# licznik.net
KiCad netlist of a schematic drawn in EAGLE
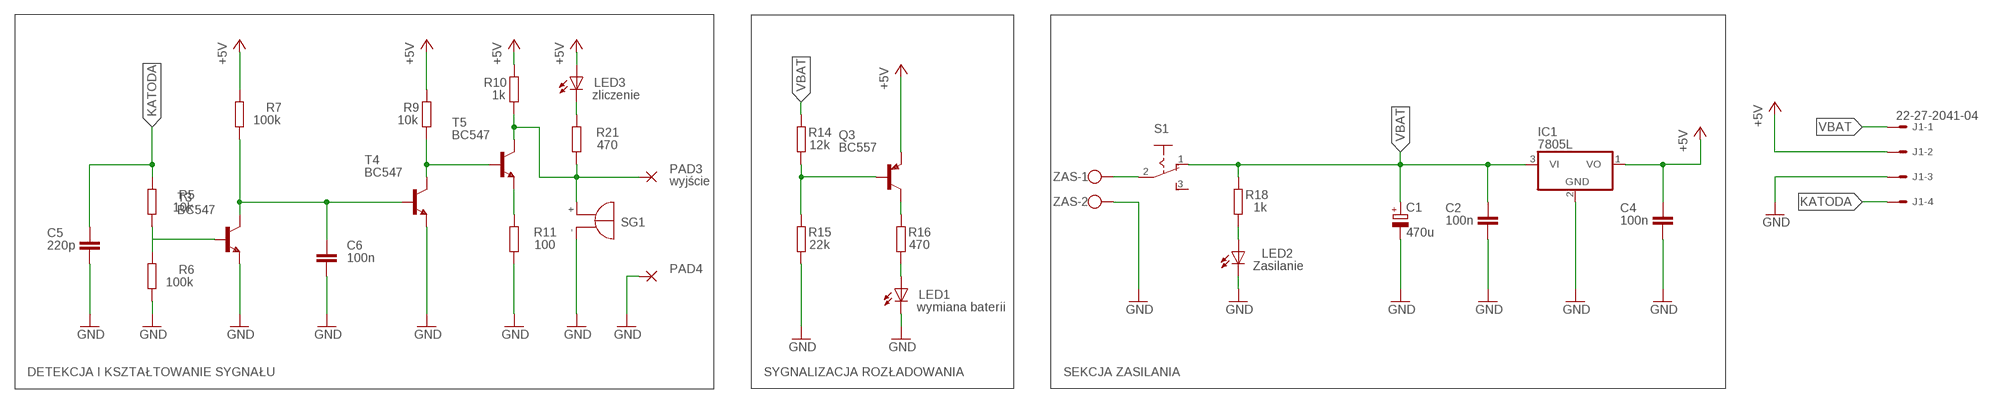
[diagram p0: schematic, sheet 1]

(export (version "E")
  (design (tool "Eeschema 10.0.6"))
  (components
    (comp (ref "C1")
      (value "470u")
      (footprint "eagle-import:E3,5-8")
      (libsource (lib "eagle-import") (part "CPOL-EUE3.5-8"))
    )
    (comp (ref "C2")
      (value "100n")
      (footprint "eagle-import:C5B3")
      (libsource (lib "eagle-import") (part "C5/3"))
    )
    (comp (ref "C4")
      (value "100n")
      (footprint "eagle-import:C5B3")
      (libsource (lib "eagle-import") (part "C5/3"))
    )
    (comp (ref "C5")
      (value "220p")
      (footprint "eagle-import:C5B3")
      (libsource (lib "eagle-import") (part "C5/3"))
    )
    (comp (ref "C6")
      (value "100n")
      (footprint "eagle-import:C5B3")
      (libsource (lib "eagle-import") (part "C5/3"))
    )
    (comp (ref "IC1")
      (value "7805L")
      (footprint "eagle-import:TO92")
      (libsource (lib "eagle-import") (part "78L05"))
    )
    (comp (ref "J1")
      (value "22-27-2041-04")
      (footprint "eagle-import:6410-04")
      (libsource (lib "eagle-import") (part "22-?-0427-2041"))
    )
    (comp (ref "LED1")
      (value "wymiana baterii")
      (footprint "eagle-import:LED3MM")
      (libsource (lib "eagle-import") (part "LED3MM"))
    )
    (comp (ref "LED2")
      (value "Zasilanie")
      (footprint "eagle-import:LED3MM")
      (libsource (lib "eagle-import") (part "LED3MM"))
    )
    (comp (ref "LED3")
      (value "zliczenie")
      (footprint "eagle-import:LED3MM")
      (libsource (lib "eagle-import") (part "LED3MM"))
    )
    (comp (ref "PAD3")
      (value "wyjście")
      (footprint "eagle-import:2,15_1,0")
      (libsource (lib "eagle-import") (part "WIREPAD2,15/1,0"))
    )
    (comp (ref "PAD4")
      (value "WIREPAD2,15/1,0")
      (footprint "eagle-import:2,15_1,0")
      (libsource (lib "eagle-import") (part "WIREPAD2,15/1,0"))
    )
    (comp (ref "Q3")
      (value "BC557")
      (footprint "eagle-import:TO92")
      (libsource (lib "eagle-import") (part "BC557"))
    )
    (comp (ref "R5")
      (value "10k")
      (footprint "eagle-import:0207_10")
      (libsource (lib "eagle-import") (part "R-EU_0207/10"))
    )
    (comp (ref "R6")
      (value "100k")
      (footprint "eagle-import:0207_10")
      (libsource (lib "eagle-import") (part "R-EU_0207/10"))
    )
    (comp (ref "R7")
      (value "100k")
      (footprint "eagle-import:0207_10")
      (libsource (lib "eagle-import") (part "R-EU_0207/10"))
    )
    (comp (ref "R9")
      (value "10k")
      (footprint "eagle-import:0207_10")
      (libsource (lib "eagle-import") (part "R-EU_0207/10"))
    )
    (comp (ref "R10")
      (value "1k")
      (footprint "eagle-import:0207_10")
      (libsource (lib "eagle-import") (part "R-EU_0207/10"))
    )
    (comp (ref "R11")
      (value "100")
      (footprint "eagle-import:0207_10")
      (libsource (lib "eagle-import") (part "R-EU_0207/10"))
    )
    (comp (ref "R14")
      (value "12k")
      (footprint "eagle-import:0207_10")
      (libsource (lib "eagle-import") (part "R-EU_0207/10"))
    )
    (comp (ref "R15")
      (value "22k")
      (footprint "eagle-import:0207_10")
      (libsource (lib "eagle-import") (part "R-EU_0207/10"))
    )
    (comp (ref "R16")
      (value "470")
      (footprint "eagle-import:0207_10")
      (libsource (lib "eagle-import") (part "R-EU_0207/10"))
    )
    (comp (ref "R18")
      (value "1k")
      (footprint "eagle-import:0207_10")
      (libsource (lib "eagle-import") (part "R-EU_0207/10"))
    )
    (comp (ref "R21")
      (value "470")
      (footprint "eagle-import:0207_10")
      (libsource (lib "eagle-import") (part "R-EU_0207/10"))
    )
    (comp (ref "S1")
      (value "255SB")
      (footprint "eagle-import:255SB")
      (libsource (lib "eagle-import") (part "255SB"))
    )
    (comp (ref "SG1")
      (value "F/QMBIII")
      (footprint "eagle-import:F_QMBIII")
      (libsource (lib "eagle-import") (part "F/QMBIII"))
    )
    (comp (ref "T3")
      (value "BC547")
      (footprint "eagle-import:TO92")
      (libsource (lib "eagle-import") (part "BC547"))
    )
    (comp (ref "T4")
      (value "BC547")
      (footprint "eagle-import:TO92")
      (libsource (lib "eagle-import") (part "BC547"))
    )
    (comp (ref "T5")
      (value "BC547")
      (footprint "eagle-import:TO92")
      (libsource (lib "eagle-import") (part "BC547"))
    )
    (comp (ref "ZAS")
      (value "W237-102")
      (footprint "eagle-import:W237-102")
      (fields (field (name "MPN") "237-102"))
      (libsource (lib "eagle-import") (part "W237-102"))
    )
  )
  (nets
    (net (code "1") (name "+5V") (class "Default")
      (node (ref "C4") (pin "1") (pinfunction "1_1") (pintype "passive"))
      (node (ref "IC1") (pin "1") (pinfunction "VO_1") (pintype "passive"))
      (node (ref "J1") (pin "2") (pinfunction "S_2") (pintype "passive"))
      (node (ref "LED3") (pin "A") (pinfunction "A_A") (pintype "passive"))
      (node (ref "Q3") (pin "1") (pinfunction "E_1") (pintype "passive"))
      (node (ref "R10") (pin "2") (pinfunction "2_2") (pintype "passive"))
      (node (ref "R7") (pin "2") (pinfunction "2_2") (pintype "passive"))
      (node (ref "R9") (pin "2") (pinfunction "2_2") (pintype "passive"))
    )
    (net (code "2") (name "GND") (class "Default")
      (node (ref "C1") (pin "-") (pinfunction "-_-") (pintype "passive"))
      (node (ref "C2") (pin "2") (pinfunction "2_2") (pintype "passive"))
      (node (ref "C4") (pin "2") (pinfunction "2_2") (pintype "passive"))
      (node (ref "C5") (pin "2") (pinfunction "2_2") (pintype "passive"))
      (node (ref "C6") (pin "2") (pinfunction "2_2") (pintype "passive"))
      (node (ref "IC1") (pin "2") (pinfunction "GND_2") (pintype "passive"))
      (node (ref "J1") (pin "3") (pinfunction "S_3") (pintype "passive"))
      (node (ref "LED1") (pin "K") (pinfunction "C_K") (pintype "passive"))
      (node (ref "LED2") (pin "K") (pinfunction "C_K") (pintype "passive"))
      (node (ref "PAD4") (pin "1") (pinfunction "P_1") (pintype "passive"))
      (node (ref "R11") (pin "1") (pinfunction "1_1") (pintype "passive"))
      (node (ref "R15") (pin "1") (pinfunction "1_1") (pintype "passive"))
      (node (ref "R6") (pin "1") (pinfunction "1_1") (pintype "passive"))
      (node (ref "SG1") (pin "-") (pinfunction "+_-") (pintype "passive"))
      (node (ref "T3") (pin "1") (pinfunction "E_1") (pintype "passive"))
      (node (ref "T4") (pin "1") (pinfunction "E_1") (pintype "passive"))
      (node (ref "ZAS") (pin "2") (pinfunction "KL_2") (pintype "passive"))
    )
    (net (code "3") (name "KATODA") (class "Default")
      (node (ref "C5") (pin "1") (pinfunction "1_1") (pintype "passive"))
      (node (ref "J1") (pin "4") (pinfunction "S_4") (pintype "passive"))
      (node (ref "R5") (pin "2") (pinfunction "2_2") (pintype "passive"))
    )
    (net (code "4") (name "Net-(LED1-PadA)") (class "Default")
      (node (ref "LED1") (pin "A") (pinfunction "A_A") (pintype "passive"))
      (node (ref "R16") (pin "1") (pinfunction "1_1") (pintype "passive"))
    )
    (net (code "5") (name "Net-(LED2-PadA)") (class "Default")
      (node (ref "LED2") (pin "A") (pinfunction "A_A") (pintype "passive"))
      (node (ref "R18") (pin "1") (pinfunction "1_1") (pintype "passive"))
    )
    (net (code "6") (name "Net-(LED3-C)") (class "Default")
      (node (ref "LED3") (pin "K") (pinfunction "C_K") (pintype "passive"))
      (node (ref "R21") (pin "2") (pinfunction "2_2") (pintype "passive"))
    )
    (net (code "7") (name "Net-(PAD3-P)") (class "Default")
      (node (ref "PAD3") (pin "1") (pinfunction "P_1") (pintype "passive"))
      (node (ref "R10") (pin "1") (pinfunction "1_1") (pintype "passive"))
      (node (ref "R21") (pin "1") (pinfunction "1_1") (pintype "passive"))
      (node (ref "SG1") (pin "+") (pinfunction "-_+") (pintype "passive"))
      (node (ref "T5") (pin "3") (pinfunction "C_3") (pintype "passive"))
    )
    (net (code "8") (name "Net-(Q3-B)") (class "Default")
      (node (ref "Q3") (pin "2") (pinfunction "B_2") (pintype "passive"))
      (node (ref "R14") (pin "1") (pinfunction "1_1") (pintype "passive"))
      (node (ref "R15") (pin "2") (pinfunction "2_2") (pintype "passive"))
    )
    (net (code "9") (name "Net-(Q3-C)") (class "Default")
      (node (ref "Q3") (pin "3") (pinfunction "C_3") (pintype "passive"))
      (node (ref "R16") (pin "2") (pinfunction "2_2") (pintype "passive"))
    )
    (net (code "10") (name "Net-(S1-P)") (class "Default")
      (node (ref "S1") (pin "2") (pinfunction "P_2") (pintype "passive"))
      (node (ref "ZAS") (pin "1") (pinfunction "KL_1") (pintype "passive"))
    )
    (net (code "11") (name "Net-(T3-B)") (class "Default")
      (node (ref "R5") (pin "1") (pinfunction "1_1") (pintype "passive"))
      (node (ref "R6") (pin "2") (pinfunction "2_2") (pintype "passive"))
      (node (ref "T3") (pin "2") (pinfunction "B_2") (pintype "passive"))
    )
    (net (code "12") (name "Net-(T3-C)") (class "Default")
      (node (ref "C6") (pin "1") (pinfunction "1_1") (pintype "passive"))
      (node (ref "R7") (pin "1") (pinfunction "1_1") (pintype "passive"))
      (node (ref "T3") (pin "3") (pinfunction "C_3") (pintype "passive"))
      (node (ref "T4") (pin "2") (pinfunction "B_2") (pintype "passive"))
    )
    (net (code "13") (name "Net-(T4-C)") (class "Default")
      (node (ref "R9") (pin "1") (pinfunction "1_1") (pintype "passive"))
      (node (ref "T4") (pin "3") (pinfunction "C_3") (pintype "passive"))
      (node (ref "T5") (pin "2") (pinfunction "B_2") (pintype "passive"))
    )
    (net (code "14") (name "Net-(T5-E)") (class "Default")
      (node (ref "R11") (pin "2") (pinfunction "2_2") (pintype "passive"))
      (node (ref "T5") (pin "1") (pinfunction "E_1") (pintype "passive"))
    )
    (net (code "15") (name "VBAT") (class "Default")
      (node (ref "C1") (pin "+") (pinfunction "+_+") (pintype "passive"))
      (node (ref "C2") (pin "1") (pinfunction "1_1") (pintype "passive"))
      (node (ref "IC1") (pin "3") (pinfunction "VI_3") (pintype "input"))
      (node (ref "J1") (pin "1") (pinfunction "S_1") (pintype "passive"))
      (node (ref "R14") (pin "2") (pinfunction "2_2") (pintype "passive"))
      (node (ref "R18") (pin "2") (pinfunction "2_2") (pintype "passive"))
      (node (ref "S1") (pin "1") (pinfunction "O_1") (pintype "passive"))
    )
    (net (code "16") (name "unconnected-(S1-S-Pad3)") (class "Default")
      (node (ref "S1") (pin "3") (pinfunction "S_3") (pintype "passive"))
    )
  )
)
